# LED_Driver_-_3.net
KiCad netlist of a schematic drawn in Altium Designer
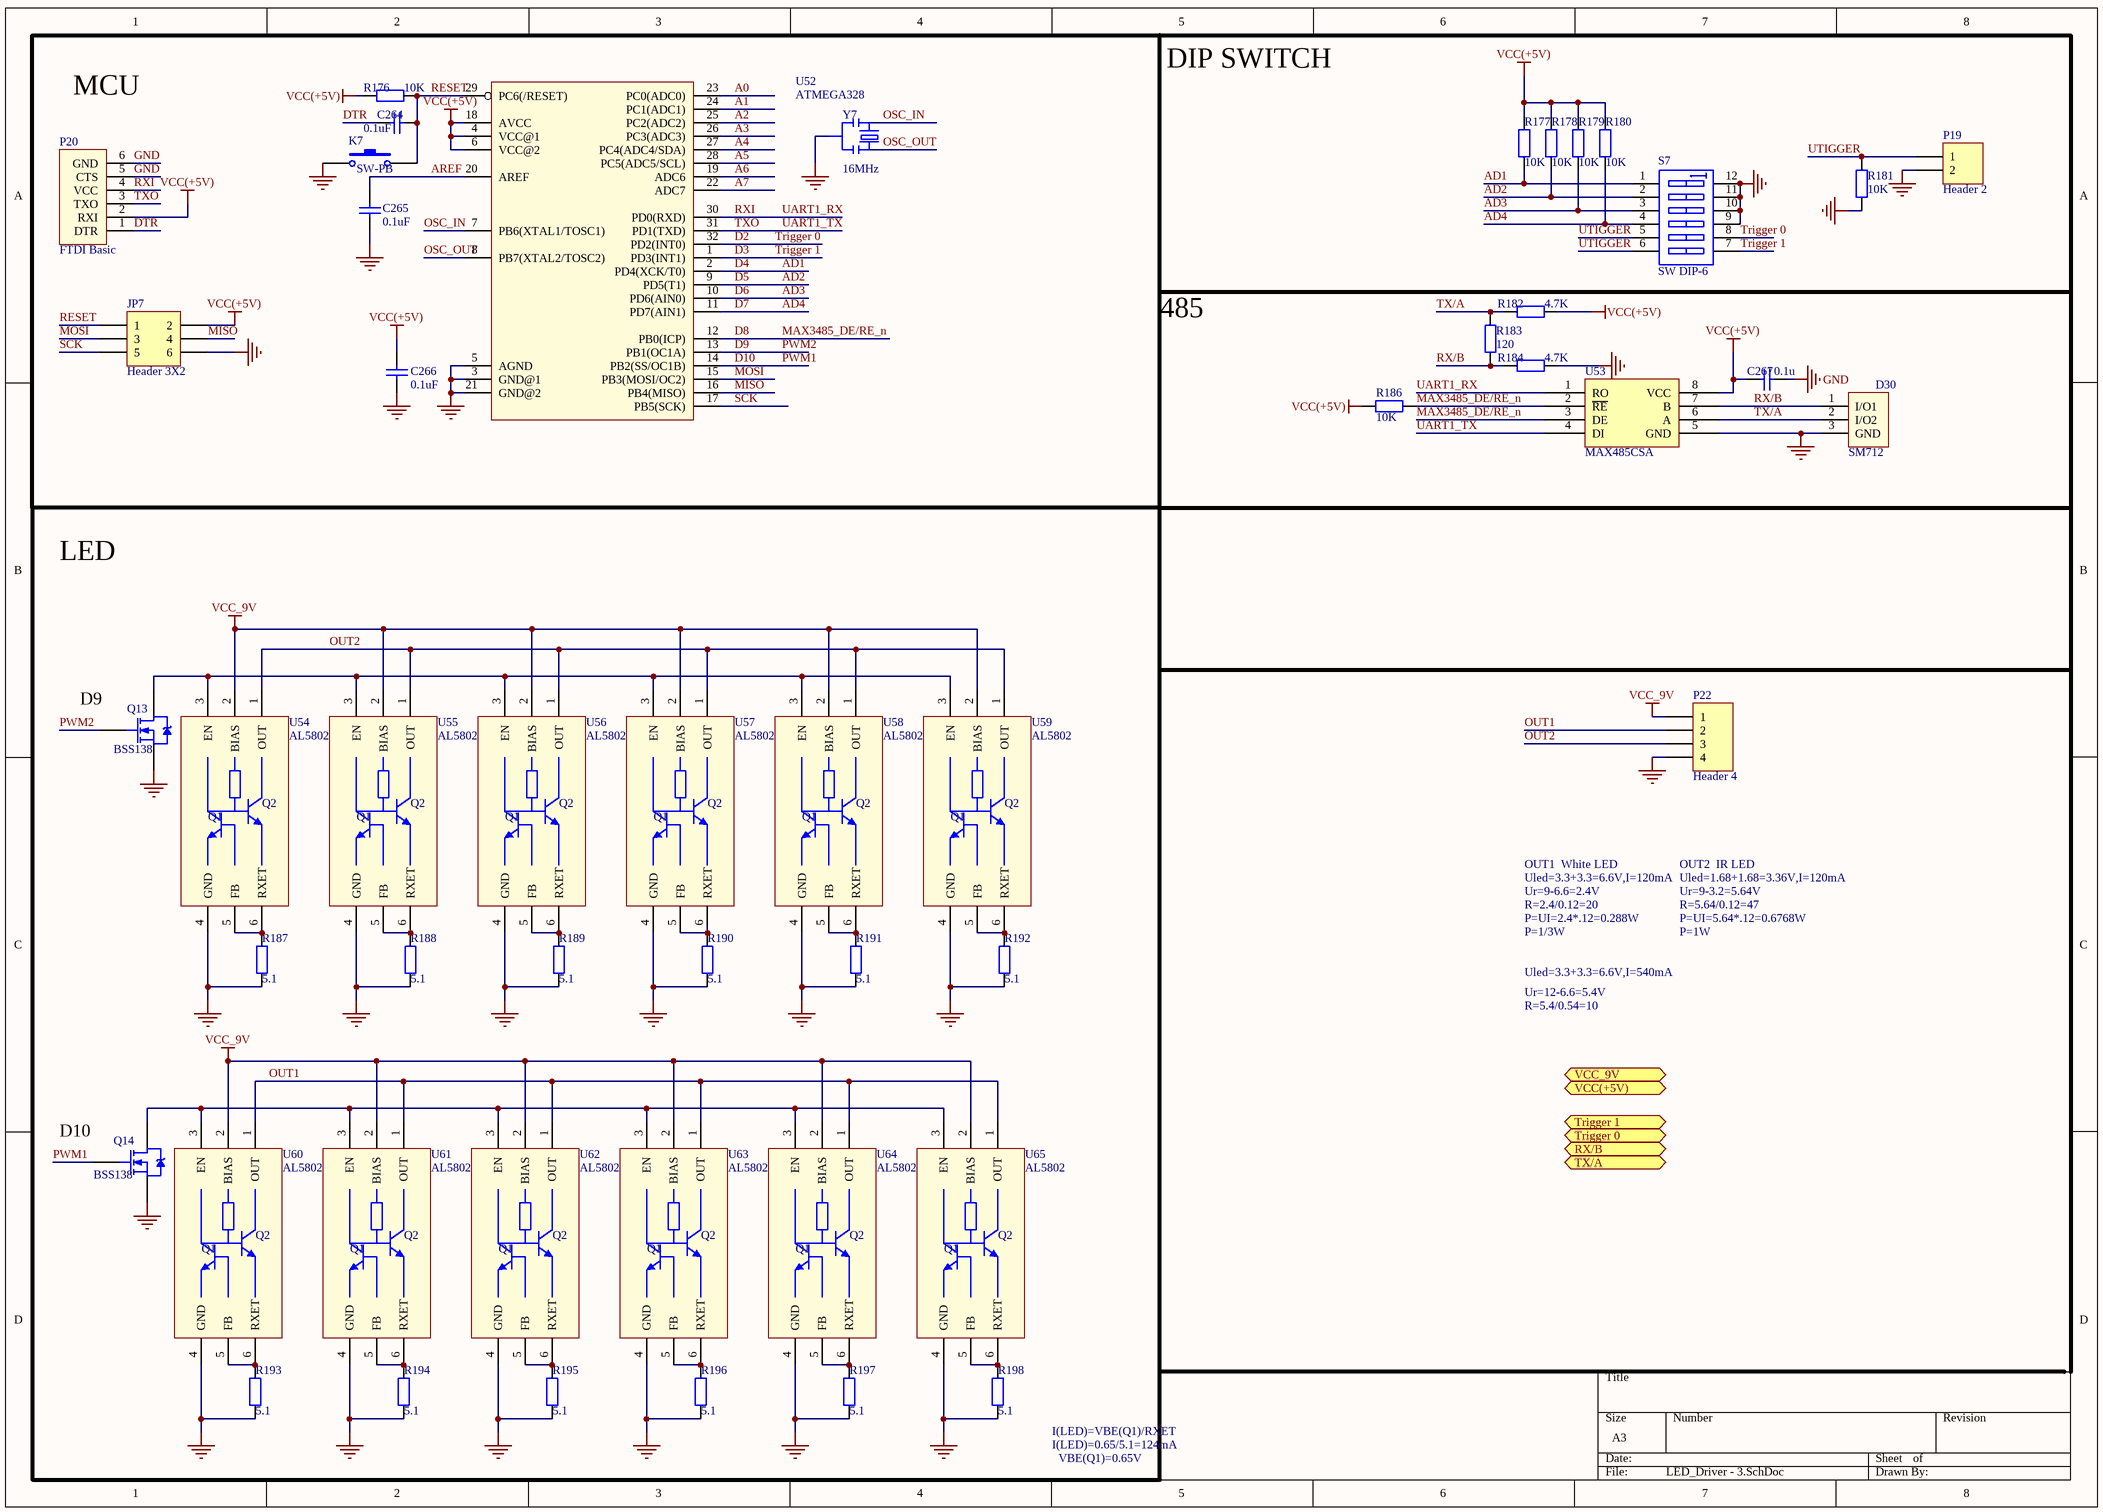
[diagram p0: LED_Driver - 3.SchDoc]

(export (version "E")
  (design (tool "Eeschema 10.0.6"))
  (components
    (comp (ref "C264")
      (value "0.1uF")
      (footprint "C0603")
      (description "Capacitor")
      (fields (field (name "IPARTNUMBER") "C100nF25V10%X7R") (field (name "VOLTAGE") "25V"))
      (libsource (lib "Schlib1") (part "CAP SMT C100nF25V10%X7R"))
    )
    (comp (ref "C265")
      (value "0.1uF")
      (footprint "C0603")
      (description "Capacitor")
      (fields (field (name "IPARTNUMBER") "C100nF25V10%X7R") (field (name "VOLTAGE") "25V"))
      (libsource (lib "Schlib1") (part "CAP SMT C100nF25V10%X7R"))
    )
    (comp (ref "C266")
      (value "0.1uF")
      (footprint "C0603")
      (description "Capacitor")
      (fields (field (name "IPARTNUMBER") "C100nF25V10%X7R") (field (name "VOLTAGE") "25V"))
      (libsource (lib "Schlib1") (part "CAP SMT C100nF25V10%X7R"))
    )
    (comp (ref "C267")
      (value "0.1u")
      (footprint "C0603")
      (description "Capacitor")
      (fields (field (name "PUBLISHER") "Altium Limited"))
      (libsource (lib "Miscellaneous Devices") (part "Cap"))
    )
    (comp (ref "D30")
      (value "SM712")
      (footprint "SOT23-3")
      (libsource (lib "STM32F4_CAM V2.0") (part "SM712"))
    )
    (comp (ref "JP7")
      (value "Header 3X2")
      (footprint "MHDR1X6")
      (description "Header, 3-Pin, Dual row")
      (fields (field (name "PUBLISHER") "Altium Limited"))
      (libsource (lib "Miscellaneous Connectors") (part "Header 3X2"))
    )
    (comp (ref "K7")
      (value "SW-PB")
      (footprint "157SW")
      (description "Switch")
      (fields (field (name "PUBLISHER") "Altium Limited"))
      (libsource (lib "Miscellaneous Devices") (part "SW-PB"))
    )
    (comp (ref "P19")
      (value "Header 2")
      (footprint "HDR1X2")
      (description "Header, 2-Pin")
      (fields (field (name "PUBLISHER") "Altium Limited"))
      (libsource (lib "Miscellaneous Connectors") (part "Header 2"))
    )
    (comp (ref "P20")
      (value "FTDI Basic")
      (footprint "MHDR1X6")
      (libsource (lib "PCB_Project1") (part "ARDUINO_SERIAL_PROGRAMPTH"))
    )
    (comp (ref "P22")
      (value "Header 4")
      (footprint "SMT_1.25MM*4")
      (description "Header, 4-Pin")
      (fields (field (name "PUBLISHER") "Altium Limited"))
      (libsource (lib "Miscellaneous Connectors") (part "Header 4"))
    )
    (comp (ref "Q13")
      (value "BSS138")
      (footprint "SOT-23 (Standard)")
      (fields
        (field (name "MANUFACTURER") "Fairchild Semiconductor")
        (field (name "MANUFACTURER PART NUMBER") "BSS123")
      )
      (libsource (lib "Miscellaneous_Devices") (part "NMOS"))
    )
    (comp (ref "Q14")
      (value "BSS138")
      (footprint "SOT-23 (Standard)")
      (fields
        (field (name "MANUFACTURER") "Fairchild Semiconductor")
        (field (name "MANUFACTURER PART NUMBER") "BSS123")
      )
      (libsource (lib "Miscellaneous_Devices") (part "NMOS"))
    )
    (comp (ref "R176")
      (value "10K")
      (footprint "R0603")
      (description "Resistor")
      (libsource (lib "") (part "Res2_2"))
    )
    (comp (ref "R177")
      (value "10K")
      (footprint "R0603")
      (description "Resistor")
      (libsource (lib "DM642") (part "Res2"))
    )
    (comp (ref "R178")
      (value "10K")
      (footprint "R0603")
      (description "Resistor")
      (libsource (lib "DM642") (part "Res2"))
    )
    (comp (ref "R179")
      (value "10K")
      (footprint "R0603")
      (description "Resistor")
      (libsource (lib "DM642") (part "Res2"))
    )
    (comp (ref "R180")
      (value "10K")
      (footprint "R0603")
      (description "Resistor")
      (libsource (lib "DM642") (part "Res2"))
    )
    (comp (ref "R181")
      (value "10K")
      (footprint "R0603")
      (description "Resistor")
      (fields (field (name "PUBLISHER") "Altium Limited"))
      (libsource (lib "Miscellaneous Devices") (part "Res2"))
    )
    (comp (ref "R182")
      (value "4.7K")
      (footprint "R0603")
      (description "Resistor")
      (libsource (lib "") (part "Res2_1"))
    )
    (comp (ref "R183")
      (value "120")
      (footprint "R0603")
      (description "Resistor")
      (libsource (lib "DM642") (part "Res2"))
    )
    (comp (ref "R184")
      (value "4.7K")
      (footprint "R0603")
      (description "Resistor")
      (libsource (lib "") (part "Res2_1"))
    )
    (comp (ref "R186")
      (value "10K")
      (footprint "R0603")
      (description "Resistor")
      (libsource (lib "") (part "Res2_1"))
    )
    (comp (ref "R187")
      (value "5.1")
      (footprint "R0603")
      (description "Resistor")
      (libsource (lib "DM642") (part "Res2"))
    )
    (comp (ref "R188")
      (value "5.1")
      (footprint "R0603")
      (description "Resistor")
      (libsource (lib "DM642") (part "Res2"))
    )
    (comp (ref "R189")
      (value "5.1")
      (footprint "R0603")
      (description "Resistor")
      (libsource (lib "DM642") (part "Res2"))
    )
    (comp (ref "R190")
      (value "5.1")
      (footprint "R0603")
      (description "Resistor")
      (libsource (lib "DM642") (part "Res2"))
    )
    (comp (ref "R191")
      (value "5.1")
      (footprint "R0603")
      (description "Resistor")
      (libsource (lib "DM642") (part "Res2"))
    )
    (comp (ref "R192")
      (value "5.1")
      (footprint "R0603")
      (description "Resistor")
      (libsource (lib "DM642") (part "Res2"))
    )
    (comp (ref "R193")
      (value "5.1")
      (footprint "R0603")
      (description "Resistor")
      (libsource (lib "DM642") (part "Res2"))
    )
    (comp (ref "R194")
      (value "5.1")
      (footprint "R0603")
      (description "Resistor")
      (libsource (lib "DM642") (part "Res2"))
    )
    (comp (ref "R195")
      (value "5.1")
      (footprint "R0603")
      (description "Resistor")
      (libsource (lib "DM642") (part "Res2"))
    )
    (comp (ref "R196")
      (value "5.1")
      (footprint "R0603")
      (description "Resistor")
      (libsource (lib "DM642") (part "Res2"))
    )
    (comp (ref "R197")
      (value "5.1")
      (footprint "R0603")
      (description "Resistor")
      (libsource (lib "DM642") (part "Res2"))
    )
    (comp (ref "R198")
      (value "5.1")
      (footprint "R0603")
      (description "Resistor")
      (libsource (lib "DM642") (part "Res2"))
    )
    (comp (ref "S7")
      (value "SW DIP-6")
      (footprint "DIP_SW_6WAY_SMD")
      (description "DIP Switch, 6 Position, SPST")
      (fields (field (name "PUBLISHER") "Altium Limited"))
      (libsource (lib "Miscellaneous Devices") (part "SW DIP-6"))
    )
    (comp (ref "U52")
      (value "ATMEGA328")
      (footprint "TQFP32-08")
      (libsource (lib "PCB_Project1") (part "ATMEGA168"))
    )
    (comp (ref "U53")
      (value "MAX485CSA")
      (footprint "SOIC-8")
      (libsource (lib "STM32F4_CAM V1.2") (part "MAX3485CSA"))
    )
    (comp (ref "U54") (value "AL5802") (footprint "SOT26") (libsource (lib "LED") (part "AL5802")))
    (comp (ref "U55") (value "AL5802") (footprint "SOT26") (libsource (lib "LED") (part "AL5802")))
    (comp (ref "U56") (value "AL5802") (footprint "SOT26") (libsource (lib "LED") (part "AL5802")))
    (comp (ref "U57") (value "AL5802") (footprint "SOT26") (libsource (lib "LED") (part "AL5802")))
    (comp (ref "U58") (value "AL5802") (footprint "SOT26") (libsource (lib "LED") (part "AL5802")))
    (comp (ref "U59") (value "AL5802") (footprint "SOT26") (libsource (lib "LED") (part "AL5802")))
    (comp (ref "U60") (value "AL5802") (footprint "SOT26") (libsource (lib "LED") (part "AL5802")))
    (comp (ref "U61") (value "AL5802") (footprint "SOT26") (libsource (lib "LED") (part "AL5802")))
    (comp (ref "U62") (value "AL5802") (footprint "SOT26") (libsource (lib "LED") (part "AL5802")))
    (comp (ref "U63") (value "AL5802") (footprint "SOT26") (libsource (lib "LED") (part "AL5802")))
    (comp (ref "U64") (value "AL5802") (footprint "SOT26") (libsource (lib "LED") (part "AL5802")))
    (comp (ref "U65") (value "AL5802") (footprint "SOT26") (libsource (lib "LED") (part "AL5802")))
    (comp (ref "Y7")
      (value "16MHz")
      (footprint "RESONATOR-SMD")
      (libsource (lib "SparkFun") (part "RESONATORSMD"))
    )
  )
  (nets
    (net (code "1") (name "/A0") (class "Default")
      (node (ref "U52") (pin "23") (pinfunction "PC0(ADC0)_23") (pintype "passive"))
    )
    (net (code "2") (name "/A1") (class "Default")
      (node (ref "U52") (pin "24") (pinfunction "PC1(ADC1)_24") (pintype "passive"))
    )
    (net (code "3") (name "/A2") (class "Default")
      (node (ref "U52") (pin "25") (pinfunction "PC2(ADC2)_25") (pintype "passive"))
    )
    (net (code "4") (name "/A3") (class "Default")
      (node (ref "U52") (pin "26") (pinfunction "PC3(ADC3)_26") (pintype "passive"))
    )
    (net (code "5") (name "/A4") (class "Default")
      (node (ref "U52") (pin "27") (pinfunction "PC4(ADC4/SDA)_27") (pintype "passive"))
    )
    (net (code "6") (name "/A5") (class "Default")
      (node (ref "U52") (pin "28") (pinfunction "PC5(ADC5/SCL)_28") (pintype "passive"))
    )
    (net (code "7") (name "/A6") (class "Default")
      (node (ref "U52") (pin "19") (pinfunction "ADC6_19") (pintype "passive"))
    )
    (net (code "8") (name "/A7") (class "Default")
      (node (ref "U52") (pin "22") (pinfunction "ADC7_22") (pintype "passive"))
    )
    (net (code "9") (name "/AD1") (class "Default")
      (node (ref "R177") (pin "2") (pinfunction "2_2") (pintype "passive"))
      (node (ref "S7") (pin "1") (pinfunction "A1_1") (pintype "passive"))
      (node (ref "U52") (pin "2") (pinfunction "PD4(XCK/T0)_2") (pintype "passive"))
    )
    (net (code "10") (name "/AD2") (class "Default")
      (node (ref "R178") (pin "2") (pinfunction "2_2") (pintype "passive"))
      (node (ref "S7") (pin "2") (pinfunction "A2_2") (pintype "passive"))
      (node (ref "U52") (pin "9") (pinfunction "PD5(T1)_9") (pintype "passive"))
    )
    (net (code "11") (name "/AD3") (class "Default")
      (node (ref "R179") (pin "2") (pinfunction "2_2") (pintype "passive"))
      (node (ref "S7") (pin "3") (pinfunction "A3_3") (pintype "passive"))
      (node (ref "U52") (pin "10") (pinfunction "PD6(AIN0)_10") (pintype "passive"))
    )
    (net (code "12") (name "/AD4") (class "Default")
      (node (ref "R180") (pin "2") (pinfunction "2_2") (pintype "passive"))
      (node (ref "S7") (pin "4") (pinfunction "A4_4") (pintype "passive"))
      (node (ref "U52") (pin "11") (pinfunction "PD7(AIN1)_11") (pintype "passive"))
    )
    (net (code "13") (name "/AREF") (class "Default")
      (node (ref "C265") (pin "2") (pinfunction "2_2") (pintype "passive"))
      (node (ref "U52") (pin "20") (pinfunction "AREF_20") (pintype "passive"))
    )
    (net (code "14") (name "/D2") (class "Default")
      (node (ref "S7") (pin "8") (pinfunction "B5_8") (pintype "passive"))
      (node (ref "U52") (pin "32") (pinfunction "PD2(INT0)_32") (pintype "passive"))
    )
    (net (code "15") (name "/D3") (class "Default")
      (node (ref "S7") (pin "7") (pinfunction "B6_7") (pintype "passive"))
      (node (ref "U52") (pin "1") (pinfunction "PD3(INT1)_1") (pintype "passive"))
    )
    (net (code "16") (name "/D8") (class "Default")
      (node (ref "R186") (pin "1") (pinfunction "1_1") (pintype "passive"))
      (node (ref "U52") (pin "12") (pinfunction "PB0(ICP)_12") (pintype "passive"))
      (node (ref "U53") (pin "2") (pinfunction "~{RE}_2") (pintype "passive"))
      (node (ref "U53") (pin "3") (pinfunction "DE_3") (pintype "passive"))
    )
    (net (code "17") (name "/D9") (class "Default")
      (node (ref "Q13") (pin "G") (pinfunction "G_G") (pintype "passive"))
      (node (ref "U52") (pin "13") (pinfunction "PB1(OC1A)_13") (pintype "passive"))
    )
    (net (code "18") (name "/D10") (class "Default")
      (node (ref "Q14") (pin "G") (pinfunction "G_G") (pintype "passive"))
      (node (ref "U52") (pin "14") (pinfunction "PB2(SS/OC1B)_14") (pintype "passive"))
    )
    (net (code "19") (name "/DTR") (class "Default")
      (node (ref "C264") (pin "1") (pinfunction "1_1") (pintype "passive"))
      (node (ref "P20") (pin "1") (pinfunction "DTR_1") (pintype "passive"))
    )
    (net (code "20") (name "/MISO") (class "Default")
      (node (ref "JP7") (pin "4") (pinfunction "4_4") (pintype "passive"))
      (node (ref "U52") (pin "16") (pinfunction "PB4(MISO)_16") (pintype "passive"))
    )
    (net (code "21") (name "/MOSI") (class "Default")
      (node (ref "JP7") (pin "3") (pinfunction "3_3") (pintype "passive"))
      (node (ref "U52") (pin "15") (pinfunction "PB3(MOSI/OC2)_15") (pintype "passive"))
    )
    (net (code "22") (name "/OSC_IN") (class "Default")
      (node (ref "U52") (pin "7") (pinfunction "PB6(XTAL1/TOSC1)_7") (pintype "passive"))
      (node (ref "Y7") (pin "3") (pinfunction "3_3") (pintype "passive"))
    )
    (net (code "23") (name "/OSC_OUT") (class "Default")
      (node (ref "U52") (pin "8") (pinfunction "PB7(XTAL2/TOSC2)_8") (pintype "passive"))
      (node (ref "Y7") (pin "1") (pinfunction "1_1") (pintype "passive"))
    )
    (net (code "24") (name "/OUT1") (class "Default")
      (node (ref "P22") (pin "2") (pinfunction "2_2") (pintype "passive"))
      (node (ref "U60") (pin "1") (pinfunction "OUT_1") (pintype "passive"))
      (node (ref "U61") (pin "1") (pinfunction "OUT_1") (pintype "passive"))
      (node (ref "U62") (pin "1") (pinfunction "OUT_1") (pintype "passive"))
      (node (ref "U63") (pin "1") (pinfunction "OUT_1") (pintype "passive"))
      (node (ref "U64") (pin "1") (pinfunction "OUT_1") (pintype "passive"))
      (node (ref "U65") (pin "1") (pinfunction "OUT_1") (pintype "passive"))
    )
    (net (code "25") (name "/OUT2") (class "Default")
      (node (ref "P22") (pin "3") (pinfunction "3_3") (pintype "passive"))
      (node (ref "U54") (pin "1") (pinfunction "OUT_1") (pintype "passive"))
      (node (ref "U55") (pin "1") (pinfunction "OUT_1") (pintype "passive"))
      (node (ref "U56") (pin "1") (pinfunction "OUT_1") (pintype "passive"))
      (node (ref "U57") (pin "1") (pinfunction "OUT_1") (pintype "passive"))
      (node (ref "U58") (pin "1") (pinfunction "OUT_1") (pintype "passive"))
      (node (ref "U59") (pin "1") (pinfunction "OUT_1") (pintype "passive"))
    )
    (net (code "26") (name "/RESET") (class "Default")
      (node (ref "C264") (pin "2") (pinfunction "2_2") (pintype "passive"))
      (node (ref "JP7") (pin "1") (pinfunction "1_1") (pintype "passive"))
      (node (ref "K7") (pin "2") (pinfunction "2_2") (pintype "passive"))
      (node (ref "R176") (pin "2") (pinfunction "2_2") (pintype "passive"))
      (node (ref "U52") (pin "29") (pinfunction "PC6(/RESET)_29") (pintype "passive"))
    )
    (net (code "27") (name "/RXI") (class "Default")
      (node (ref "P20") (pin "4") (pinfunction "VCC_4") (pintype "passive"))
      (node (ref "U52") (pin "30") (pinfunction "PD0(RXD)_30") (pintype "passive"))
      (node (ref "U53") (pin "1") (pinfunction "RO_1") (pintype "passive"))
    )
    (net (code "28") (name "/RX{slash}B") (class "Default")
      (node (ref "D30") (pin "1") (pinfunction "I/O1_1") (pintype "passive"))
      (node (ref "R183") (pin "2") (pinfunction "2_2") (pintype "passive"))
      (node (ref "R184") (pin "2") (pinfunction "2_2") (pintype "passive"))
      (node (ref "U53") (pin "7") (pinfunction "B_7") (pintype "passive"))
    )
    (net (code "29") (name "/SCK") (class "Default")
      (node (ref "JP7") (pin "5") (pinfunction "5_5") (pintype "passive"))
      (node (ref "U52") (pin "17") (pinfunction "PB5(SCK)_17") (pintype "passive"))
    )
    (net (code "30") (name "/TXO") (class "Default")
      (node (ref "P20") (pin "3") (pinfunction "TXO_3") (pintype "passive"))
      (node (ref "U52") (pin "31") (pinfunction "PD1(TXD)_31") (pintype "passive"))
      (node (ref "U53") (pin "4") (pinfunction "DI_4") (pintype "passive"))
    )
    (net (code "31") (name "/TX{slash}A") (class "Default")
      (node (ref "D30") (pin "2") (pinfunction "I/O2_2") (pintype "passive"))
      (node (ref "R182") (pin "2") (pinfunction "2_2") (pintype "passive"))
      (node (ref "R183") (pin "1") (pinfunction "1_1") (pintype "passive"))
      (node (ref "U53") (pin "6") (pinfunction "A_6") (pintype "passive"))
    )
    (net (code "32") (name "/UTIGGER") (class "Default")
      (node (ref "P19") (pin "1") (pinfunction "1_1") (pintype "passive"))
      (node (ref "R181") (pin "2") (pinfunction "2_2") (pintype "passive"))
      (node (ref "S7") (pin "5") (pinfunction "A5_5") (pintype "passive"))
      (node (ref "S7") (pin "6") (pinfunction "A6_6") (pintype "passive"))
    )
    (net (code "33") (name "GND") (class "Default")
      (node (ref "C265") (pin "1") (pinfunction "1_1") (pintype "passive"))
      (node (ref "C266") (pin "2") (pinfunction "2_2") (pintype "passive"))
      (node (ref "C267") (pin "1") (pinfunction "1_1") (pintype "passive"))
      (node (ref "D30") (pin "3") (pinfunction "GND_3") (pintype "passive"))
      (node (ref "JP7") (pin "6") (pinfunction "6_6") (pintype "passive"))
      (node (ref "K7") (pin "1") (pinfunction "1_1") (pintype "passive"))
      (node (ref "P19") (pin "2") (pinfunction "2_2") (pintype "passive"))
      (node (ref "P20") (pin "5") (pinfunction "CTS_5") (pintype "passive"))
      (node (ref "P20") (pin "6") (pinfunction "GND_6") (pintype "passive"))
      (node (ref "P22") (pin "4") (pinfunction "4_4") (pintype "passive"))
      (node (ref "Q13") (pin "S") (pinfunction "S_S") (pintype "passive"))
      (node (ref "Q14") (pin "S") (pinfunction "S_S") (pintype "passive"))
      (node (ref "R181") (pin "1") (pinfunction "1_1") (pintype "passive"))
      (node (ref "R184") (pin "1") (pinfunction "1_1") (pintype "passive"))
      (node (ref "R187") (pin "2") (pinfunction "2_2") (pintype "passive"))
      (node (ref "R188") (pin "2") (pinfunction "2_2") (pintype "passive"))
      (node (ref "R189") (pin "2") (pinfunction "2_2") (pintype "passive"))
      (node (ref "R190") (pin "2") (pinfunction "2_2") (pintype "passive"))
      (node (ref "R191") (pin "2") (pinfunction "2_2") (pintype "passive"))
      (node (ref "R192") (pin "2") (pinfunction "2_2") (pintype "passive"))
      (node (ref "R193") (pin "2") (pinfunction "2_2") (pintype "passive"))
      (node (ref "R194") (pin "2") (pinfunction "2_2") (pintype "passive"))
      (node (ref "R195") (pin "2") (pinfunction "2_2") (pintype "passive"))
      (node (ref "R196") (pin "2") (pinfunction "2_2") (pintype "passive"))
      (node (ref "R197") (pin "2") (pinfunction "2_2") (pintype "passive"))
      (node (ref "R198") (pin "2") (pinfunction "2_2") (pintype "passive"))
      (node (ref "S7") (pin "10") (pinfunction "B3_10") (pintype "passive"))
      (node (ref "S7") (pin "11") (pinfunction "B2_11") (pintype "passive"))
      (node (ref "S7") (pin "12") (pinfunction "B1_12") (pintype "passive"))
      (node (ref "S7") (pin "9") (pinfunction "B4_9") (pintype "passive"))
      (node (ref "U52") (pin "21") (pinfunction "GND@2_21") (pintype "passive"))
      (node (ref "U52") (pin "3") (pinfunction "GND@1_3") (pintype "passive"))
      (node (ref "U52") (pin "5") (pinfunction "AGND_5") (pintype "passive"))
      (node (ref "U53") (pin "5") (pinfunction "GND_5") (pintype "passive"))
      (node (ref "U54") (pin "4") (pinfunction "GND_4") (pintype "passive"))
      (node (ref "U55") (pin "4") (pinfunction "GND_4") (pintype "passive"))
      (node (ref "U56") (pin "4") (pinfunction "GND_4") (pintype "passive"))
      (node (ref "U57") (pin "4") (pinfunction "GND_4") (pintype "passive"))
      (node (ref "U58") (pin "4") (pinfunction "GND_4") (pintype "passive"))
      (node (ref "U59") (pin "4") (pinfunction "GND_4") (pintype "passive"))
      (node (ref "U60") (pin "4") (pinfunction "GND_4") (pintype "passive"))
      (node (ref "U61") (pin "4") (pinfunction "GND_4") (pintype "passive"))
      (node (ref "U62") (pin "4") (pinfunction "GND_4") (pintype "passive"))
      (node (ref "U63") (pin "4") (pinfunction "GND_4") (pintype "passive"))
      (node (ref "U64") (pin "4") (pinfunction "GND_4") (pintype "passive"))
      (node (ref "U65") (pin "4") (pinfunction "GND_4") (pintype "passive"))
      (node (ref "Y7") (pin "2") (pinfunction "2_2") (pintype "passive"))
    )
    (net (code "34") (name "Net-(U54-EN)") (class "Default")
      (node (ref "Q13") (pin "D") (pinfunction "D_D") (pintype "passive"))
      (node (ref "U54") (pin "3") (pinfunction "EN_3") (pintype "passive"))
      (node (ref "U55") (pin "3") (pinfunction "EN_3") (pintype "passive"))
      (node (ref "U56") (pin "3") (pinfunction "EN_3") (pintype "passive"))
      (node (ref "U57") (pin "3") (pinfunction "EN_3") (pintype "passive"))
      (node (ref "U58") (pin "3") (pinfunction "EN_3") (pintype "passive"))
      (node (ref "U59") (pin "3") (pinfunction "EN_3") (pintype "passive"))
    )
    (net (code "35") (name "Net-(U54-FB)") (class "Default")
      (node (ref "R187") (pin "1") (pinfunction "1_1") (pintype "passive"))
      (node (ref "U54") (pin "5") (pinfunction "FB_5") (pintype "passive"))
      (node (ref "U54") (pin "6") (pinfunction "RXET_6") (pintype "passive"))
    )
    (net (code "36") (name "Net-(U55-FB)") (class "Default")
      (node (ref "R188") (pin "1") (pinfunction "1_1") (pintype "passive"))
      (node (ref "U55") (pin "5") (pinfunction "FB_5") (pintype "passive"))
      (node (ref "U55") (pin "6") (pinfunction "RXET_6") (pintype "passive"))
    )
    (net (code "37") (name "Net-(U56-FB)") (class "Default")
      (node (ref "R189") (pin "1") (pinfunction "1_1") (pintype "passive"))
      (node (ref "U56") (pin "5") (pinfunction "FB_5") (pintype "passive"))
      (node (ref "U56") (pin "6") (pinfunction "RXET_6") (pintype "passive"))
    )
    (net (code "38") (name "Net-(U57-FB)") (class "Default")
      (node (ref "R190") (pin "1") (pinfunction "1_1") (pintype "passive"))
      (node (ref "U57") (pin "5") (pinfunction "FB_5") (pintype "passive"))
      (node (ref "U57") (pin "6") (pinfunction "RXET_6") (pintype "passive"))
    )
    (net (code "39") (name "Net-(U58-FB)") (class "Default")
      (node (ref "R191") (pin "1") (pinfunction "1_1") (pintype "passive"))
      (node (ref "U58") (pin "5") (pinfunction "FB_5") (pintype "passive"))
      (node (ref "U58") (pin "6") (pinfunction "RXET_6") (pintype "passive"))
    )
    (net (code "40") (name "Net-(U59-FB)") (class "Default")
      (node (ref "R192") (pin "1") (pinfunction "1_1") (pintype "passive"))
      (node (ref "U59") (pin "5") (pinfunction "FB_5") (pintype "passive"))
      (node (ref "U59") (pin "6") (pinfunction "RXET_6") (pintype "passive"))
    )
    (net (code "41") (name "Net-(U60-EN)") (class "Default")
      (node (ref "Q14") (pin "D") (pinfunction "D_D") (pintype "passive"))
      (node (ref "U60") (pin "3") (pinfunction "EN_3") (pintype "passive"))
      (node (ref "U61") (pin "3") (pinfunction "EN_3") (pintype "passive"))
      (node (ref "U62") (pin "3") (pinfunction "EN_3") (pintype "passive"))
      (node (ref "U63") (pin "3") (pinfunction "EN_3") (pintype "passive"))
      (node (ref "U64") (pin "3") (pinfunction "EN_3") (pintype "passive"))
      (node (ref "U65") (pin "3") (pinfunction "EN_3") (pintype "passive"))
    )
    (net (code "42") (name "Net-(U60-FB)") (class "Default")
      (node (ref "R193") (pin "1") (pinfunction "1_1") (pintype "passive"))
      (node (ref "U60") (pin "5") (pinfunction "FB_5") (pintype "passive"))
      (node (ref "U60") (pin "6") (pinfunction "RXET_6") (pintype "passive"))
    )
    (net (code "43") (name "Net-(U61-FB)") (class "Default")
      (node (ref "R194") (pin "1") (pinfunction "1_1") (pintype "passive"))
      (node (ref "U61") (pin "5") (pinfunction "FB_5") (pintype "passive"))
      (node (ref "U61") (pin "6") (pinfunction "RXET_6") (pintype "passive"))
    )
    (net (code "44") (name "Net-(U62-FB)") (class "Default")
      (node (ref "R195") (pin "1") (pinfunction "1_1") (pintype "passive"))
      (node (ref "U62") (pin "5") (pinfunction "FB_5") (pintype "passive"))
      (node (ref "U62") (pin "6") (pinfunction "RXET_6") (pintype "passive"))
    )
    (net (code "45") (name "Net-(U63-FB)") (class "Default")
      (node (ref "R196") (pin "1") (pinfunction "1_1") (pintype "passive"))
      (node (ref "U63") (pin "5") (pinfunction "FB_5") (pintype "passive"))
      (node (ref "U63") (pin "6") (pinfunction "RXET_6") (pintype "passive"))
    )
    (net (code "46") (name "Net-(U64-FB)") (class "Default")
      (node (ref "R197") (pin "1") (pinfunction "1_1") (pintype "passive"))
      (node (ref "U64") (pin "5") (pinfunction "FB_5") (pintype "passive"))
      (node (ref "U64") (pin "6") (pinfunction "RXET_6") (pintype "passive"))
    )
    (net (code "47") (name "Net-(U65-FB)") (class "Default")
      (node (ref "R198") (pin "1") (pinfunction "1_1") (pintype "passive"))
      (node (ref "U65") (pin "5") (pinfunction "FB_5") (pintype "passive"))
      (node (ref "U65") (pin "6") (pinfunction "RXET_6") (pintype "passive"))
    )
    (net (code "48") (name "VCC(+5V)") (class "Default")
      (node (ref "C266") (pin "1") (pinfunction "1_1") (pintype "passive"))
      (node (ref "C267") (pin "2") (pinfunction "2_2") (pintype "passive"))
      (node (ref "JP7") (pin "2") (pinfunction "2_2") (pintype "passive"))
      (node (ref "P20") (pin "2") (pinfunction "RXI_2") (pintype "passive"))
      (node (ref "R176") (pin "1") (pinfunction "1_1") (pintype "passive"))
      (node (ref "R177") (pin "1") (pinfunction "1_1") (pintype "passive"))
      (node (ref "R178") (pin "1") (pinfunction "1_1") (pintype "passive"))
      (node (ref "R179") (pin "1") (pinfunction "1_1") (pintype "passive"))
      (node (ref "R180") (pin "1") (pinfunction "1_1") (pintype "passive"))
      (node (ref "R182") (pin "1") (pinfunction "1_1") (pintype "passive"))
      (node (ref "R186") (pin "2") (pinfunction "2_2") (pintype "passive"))
      (node (ref "U52") (pin "18") (pinfunction "AVCC_18") (pintype "passive"))
      (node (ref "U52") (pin "4") (pinfunction "VCC@1_4") (pintype "passive"))
      (node (ref "U52") (pin "6") (pinfunction "VCC@2_6") (pintype "passive"))
      (node (ref "U53") (pin "8") (pinfunction "VCC_8") (pintype "passive"))
    )
    (net (code "49") (name "VCC_9V") (class "Default")
      (node (ref "P22") (pin "1") (pinfunction "1_1") (pintype "passive"))
      (node (ref "U54") (pin "2") (pinfunction "BIAS_2") (pintype "passive"))
      (node (ref "U55") (pin "2") (pinfunction "BIAS_2") (pintype "passive"))
      (node (ref "U56") (pin "2") (pinfunction "BIAS_2") (pintype "passive"))
      (node (ref "U57") (pin "2") (pinfunction "BIAS_2") (pintype "passive"))
      (node (ref "U58") (pin "2") (pinfunction "BIAS_2") (pintype "passive"))
      (node (ref "U59") (pin "2") (pinfunction "BIAS_2") (pintype "passive"))
      (node (ref "U60") (pin "2") (pinfunction "BIAS_2") (pintype "passive"))
      (node (ref "U61") (pin "2") (pinfunction "BIAS_2") (pintype "passive"))
      (node (ref "U62") (pin "2") (pinfunction "BIAS_2") (pintype "passive"))
      (node (ref "U63") (pin "2") (pinfunction "BIAS_2") (pintype "passive"))
      (node (ref "U64") (pin "2") (pinfunction "BIAS_2") (pintype "passive"))
      (node (ref "U65") (pin "2") (pinfunction "BIAS_2") (pintype "passive"))
    )
  )
)
